# Interface.net
KiCad netlist of a schematic drawn in Altium Designer
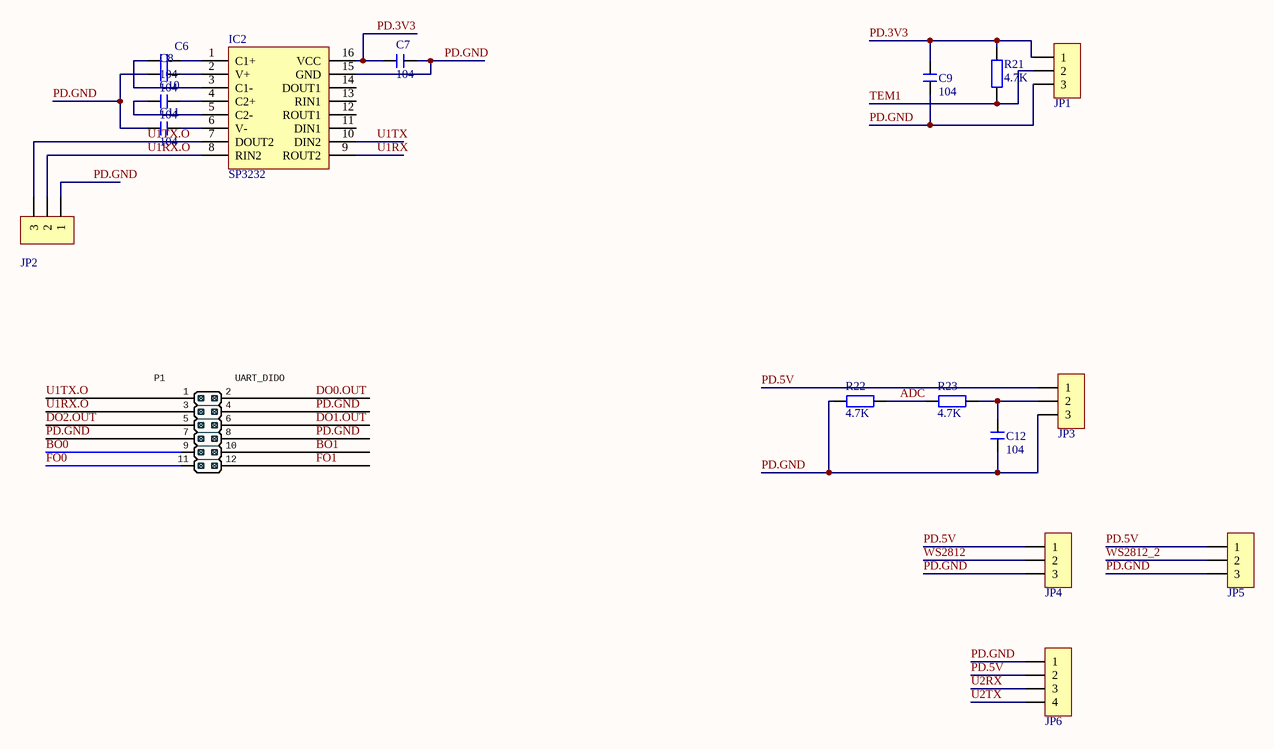
[diagram p0: Interface.SchDoc]

(export (version "E")
  (design (tool "Eeschema 10.0.6"))
  (components
    (comp (ref "C6")
      (value "104")
      (footprint "C 0603")
      (description "无极性贴片电容")
      (fields (field (name "版权归属") "源创客"))
      (libsource (lib "电阻-电容-电感") (part "C"))
    )
    (comp (ref "C7")
      (value "104")
      (footprint "C 0603")
      (description "无极性贴片电容")
      (fields (field (name "版权归属") "源创客"))
      (libsource (lib "电阻-电容-电感") (part "C"))
    )
    (comp (ref "C8")
      (value "104")
      (footprint "C 0603")
      (description "无极性贴片电容")
      (fields (field (name "版权归属") "源创客"))
      (libsource (lib "电阻-电容-电感") (part "C"))
    )
    (comp (ref "C9")
      (value "104")
      (footprint "C 0603")
      (description "无极性贴片电容")
      (fields (field (name "版权归属") "源创客"))
      (libsource (lib "电阻-电容-电感") (part "C"))
    )
    (comp (ref "C10")
      (value "104")
      (footprint "C 0603")
      (description "无极性贴片电容")
      (fields (field (name "版权归属") "源创客"))
      (libsource (lib "电阻-电容-电感") (part "C"))
    )
    (comp (ref "C11")
      (value "104")
      (footprint "C 0603")
      (description "无极性贴片电容")
      (fields (field (name "版权归属") "源创客"))
      (libsource (lib "电阻-电容-电感") (part "C"))
    )
    (comp (ref "C12")
      (value "104")
      (footprint "C 0603")
      (description "无极性贴片电容")
      (fields (field (name "版权归属") "源创客"))
      (libsource (lib "电阻-电容-电感") (part "C"))
    )
    (comp (ref "IC2")
      (value "SP3232")
      (footprint "TSSOP16_N")
      (description "RS232通讯芯片")
      (fields (field (name "版权归属") "源创客"))
      (libsource (lib "IC芯片") (part "SP3232"))
    )
    (comp (ref "JP1")
      (value "HDR-1X3")
      (footprint "WJ15EDGRC-3.81-3P")
      (description "3P接插件")
      (fields (field (name "版权归属") "源创客"))
      (libsource (lib "接插件") (part "Header 3"))
    )
    (comp (ref "JP2")
      (value "HDR-1X3")
      (footprint "XH2.54-3P")
      (description "3P接插件")
      (fields (field (name "版权归属") "源创客"))
      (libsource (lib "4.6   - 接插件-脚距2.54") (part "Header 3"))
    )
    (comp (ref "JP3")
      (value "HDR-1X3")
      (footprint "WJ15EDGRC-3.81-3P")
      (description "3P接插件")
      (fields (field (name "版权归属") "源创客"))
      (libsource (lib "接插件") (part "Header 3"))
    )
    (comp (ref "JP4")
      (value "HDR-1X3")
      (footprint "WJ15EDGRC-3.81-3P")
      (description "3P接插件")
      (fields (field (name "版权归属") "源创客"))
      (libsource (lib "接插件") (part "Header 3"))
    )
    (comp (ref "JP5")
      (value "HDR-1X3")
      (footprint "WJ15EDGRC-3.81-3P")
      (description "3P接插件")
      (fields (field (name "版权归属") "源创客"))
      (libsource (lib "接插件") (part "Header 3"))
    )
    (comp (ref "JP6")
      (value "HDR-1X4")
      (footprint "XH2.54-4P")
      (description "4P接插件")
      (fields (field (name "版权归属") "源创客"))
      (libsource (lib "接插件") (part "Header 4"))
    )
    (comp (ref "P1")
      (value "UART_DIDO")
      (footprint "KF2EDGRHM-3.81-2x6P")
      (description "P-EDG-2x6")
      (libsource (lib "Connector") (part "PIN_2xCol_6xPin"))
    )
    (comp (ref "R21")
      (value "4.7K")
      (footprint "R 0603")
      (description "贴片电阻")
      (fields (field (name "版权归属") "源创客"))
      (libsource (lib "电阻-电容-电感") (part "R"))
    )
    (comp (ref "R22")
      (value "4.7K")
      (footprint "R 0603")
      (description "贴片电阻")
      (fields (field (name "版权归属") "源创客"))
      (libsource (lib "电阻-电容-电感") (part "R"))
    )
    (comp (ref "R23")
      (value "4.7K")
      (footprint "R 0603")
      (description "贴片电阻")
      (fields (field (name "版权归属") "源创客"))
      (libsource (lib "电阻-电容-电感") (part "R"))
    )
  )
  (nets
    (net (code "1") (name "/ADC") (class "Default")
      (node (ref "R22") (pin "1") (pinfunction "1_1") (pintype "passive"))
      (node (ref "R23") (pin "2") (pinfunction "2_2") (pintype "passive"))
    )
    (net (code "2") (name "/BO0") (class "Default")
      (node (ref "P1") (pin "9") (pinfunction "9_9") (pintype "passive"))
    )
    (net (code "3") (name "/BO1") (class "Default")
      (node (ref "P1") (pin "10") (pinfunction "10_10") (pintype "passive"))
    )
    (net (code "4") (name "/DO0.OUT") (class "Default")
      (node (ref "P1") (pin "2") (pinfunction "2_2") (pintype "passive"))
    )
    (net (code "5") (name "/DO1.OUT") (class "Default")
      (node (ref "P1") (pin "6") (pinfunction "6_6") (pintype "passive"))
    )
    (net (code "6") (name "/DO2.OUT") (class "Default")
      (node (ref "P1") (pin "5") (pinfunction "5_5") (pintype "passive"))
    )
    (net (code "7") (name "/FO0") (class "Default")
      (node (ref "P1") (pin "11") (pinfunction "11_11") (pintype "passive"))
    )
    (net (code "8") (name "/FO1") (class "Default")
      (node (ref "P1") (pin "12") (pinfunction "12_12") (pintype "passive"))
    )
    (net (code "9") (name "/PD.3V3") (class "Default")
      (node (ref "C7") (pin "1") (pinfunction "1_1") (pintype "passive"))
      (node (ref "C9") (pin "2") (pinfunction "2_2") (pintype "passive"))
      (node (ref "IC2") (pin "16") (pinfunction "VCC_16") (pintype "passive"))
      (node (ref "JP1") (pin "1") (pinfunction "1_1") (pintype "passive"))
      (node (ref "R21") (pin "2") (pinfunction "2_2") (pintype "passive"))
    )
    (net (code "10") (name "/PD.5V") (class "Default")
      (node (ref "JP3") (pin "1") (pinfunction "1_1") (pintype "passive"))
      (node (ref "JP4") (pin "1") (pinfunction "1_1") (pintype "passive"))
      (node (ref "JP5") (pin "1") (pinfunction "1_1") (pintype "passive"))
      (node (ref "JP6") (pin "2") (pinfunction "2_2") (pintype "passive"))
    )
    (net (code "11") (name "/PD.GND") (class "Default")
      (node (ref "C11") (pin "1") (pinfunction "1_1") (pintype "passive"))
      (node (ref "C12") (pin "1") (pinfunction "1_1") (pintype "passive"))
      (node (ref "C7") (pin "2") (pinfunction "2_2") (pintype "passive"))
      (node (ref "C8") (pin "1") (pinfunction "1_1") (pintype "passive"))
      (node (ref "C9") (pin "1") (pinfunction "1_1") (pintype "passive"))
      (node (ref "IC2") (pin "15") (pinfunction "GND_15") (pintype "passive"))
      (node (ref "JP1") (pin "3") (pinfunction "3_3") (pintype "passive"))
      (node (ref "JP2") (pin "1") (pinfunction "1_1") (pintype "passive"))
      (node (ref "JP3") (pin "3") (pinfunction "3_3") (pintype "passive"))
      (node (ref "JP4") (pin "3") (pinfunction "3_3") (pintype "passive"))
      (node (ref "JP5") (pin "3") (pinfunction "3_3") (pintype "passive"))
      (node (ref "JP6") (pin "1") (pinfunction "1_1") (pintype "passive"))
      (node (ref "P1") (pin "4") (pinfunction "4_4") (pintype "passive"))
      (node (ref "P1") (pin "7") (pinfunction "7_7") (pintype "passive"))
      (node (ref "P1") (pin "8") (pinfunction "8_8") (pintype "passive"))
      (node (ref "R22") (pin "2") (pinfunction "2_2") (pintype "passive"))
    )
    (net (code "12") (name "/TEM1") (class "Default")
      (node (ref "JP1") (pin "2") (pinfunction "2_2") (pintype "passive"))
      (node (ref "R21") (pin "1") (pinfunction "1_1") (pintype "passive"))
    )
    (net (code "13") (name "/U1RX") (class "Default")
      (node (ref "IC2") (pin "9") (pinfunction "ROUT2_9") (pintype "passive"))
    )
    (net (code "14") (name "/U1RX.O") (class "Default")
      (node (ref "IC2") (pin "8") (pinfunction "RIN2_8") (pintype "passive"))
      (node (ref "JP2") (pin "2") (pinfunction "2_2") (pintype "passive"))
      (node (ref "P1") (pin "3") (pinfunction "3_3") (pintype "passive"))
    )
    (net (code "15") (name "/U1TX") (class "Default")
      (node (ref "IC2") (pin "10") (pinfunction "DIN2_10") (pintype "passive"))
    )
    (net (code "16") (name "/U1TX.O") (class "Default")
      (node (ref "IC2") (pin "7") (pinfunction "DOUT2_7") (pintype "passive"))
      (node (ref "JP2") (pin "3") (pinfunction "3_3") (pintype "passive"))
      (node (ref "P1") (pin "1") (pinfunction "1_1") (pintype "passive"))
    )
    (net (code "17") (name "/U2RX") (class "Default")
      (node (ref "JP6") (pin "3") (pinfunction "3_3") (pintype "passive"))
    )
    (net (code "18") (name "/U2TX") (class "Default")
      (node (ref "JP6") (pin "4") (pinfunction "4_4") (pintype "passive"))
    )
    (net (code "19") (name "/WS2812") (class "Default")
      (node (ref "JP4") (pin "2") (pinfunction "2_2") (pintype "passive"))
    )
    (net (code "20") (name "/WS2812_2") (class "Default")
      (node (ref "JP5") (pin "2") (pinfunction "2_2") (pintype "passive"))
    )
    (net (code "21") (name "Net-(C12-Pad2)") (class "Default")
      (node (ref "C12") (pin "2") (pinfunction "2_2") (pintype "passive"))
      (node (ref "JP3") (pin "2") (pinfunction "2_2") (pintype "passive"))
      (node (ref "R23") (pin "1") (pinfunction "1_1") (pintype "passive"))
    )
    (net (code "22") (name "Net-(IC2-C1+)") (class "Default")
      (node (ref "C6") (pin "2") (pinfunction "2_2") (pintype "passive"))
      (node (ref "IC2") (pin "1") (pinfunction "C1+_1") (pintype "passive"))
    )
    (net (code "23") (name "Net-(IC2-C1-)") (class "Default")
      (node (ref "C6") (pin "1") (pinfunction "1_1") (pintype "passive"))
      (node (ref "IC2") (pin "3") (pinfunction "C1-_3") (pintype "passive"))
    )
    (net (code "24") (name "Net-(IC2-C2+)") (class "Default")
      (node (ref "C10") (pin "2") (pinfunction "2_2") (pintype "passive"))
      (node (ref "IC2") (pin "4") (pinfunction "C2+_4") (pintype "passive"))
    )
    (net (code "25") (name "Net-(IC2-C2-)") (class "Default")
      (node (ref "C10") (pin "1") (pinfunction "1_1") (pintype "passive"))
      (node (ref "IC2") (pin "5") (pinfunction "C2-_5") (pintype "passive"))
    )
    (net (code "26") (name "Net-(IC2-V+)") (class "Default")
      (node (ref "C8") (pin "2") (pinfunction "2_2") (pintype "passive"))
      (node (ref "IC2") (pin "2") (pinfunction "V+_2") (pintype "passive"))
    )
    (net (code "27") (name "Net-(IC2-V-)") (class "Default")
      (node (ref "C11") (pin "2") (pinfunction "2_2") (pintype "passive"))
      (node (ref "IC2") (pin "6") (pinfunction "V-_6") (pintype "passive"))
    )
    (net (code "28") (name "unconnected-(IC2-DIN1-Pad11)") (class "Default")
      (node (ref "IC2") (pin "11") (pinfunction "DIN1_11") (pintype "passive"))
    )
    (net (code "29") (name "unconnected-(IC2-DOUT1-Pad14)") (class "Default")
      (node (ref "IC2") (pin "14") (pinfunction "DOUT1_14") (pintype "passive"))
    )
    (net (code "30") (name "unconnected-(IC2-RIN1-Pad13)") (class "Default")
      (node (ref "IC2") (pin "13") (pinfunction "RIN1_13") (pintype "passive"))
    )
    (net (code "31") (name "unconnected-(IC2-ROUT1-Pad12)") (class "Default")
      (node (ref "IC2") (pin "12") (pinfunction "ROUT1_12") (pintype "passive"))
    )
  )
)
